# icesio2.net
KiCad netlist of a schematic drawn in EAGLE
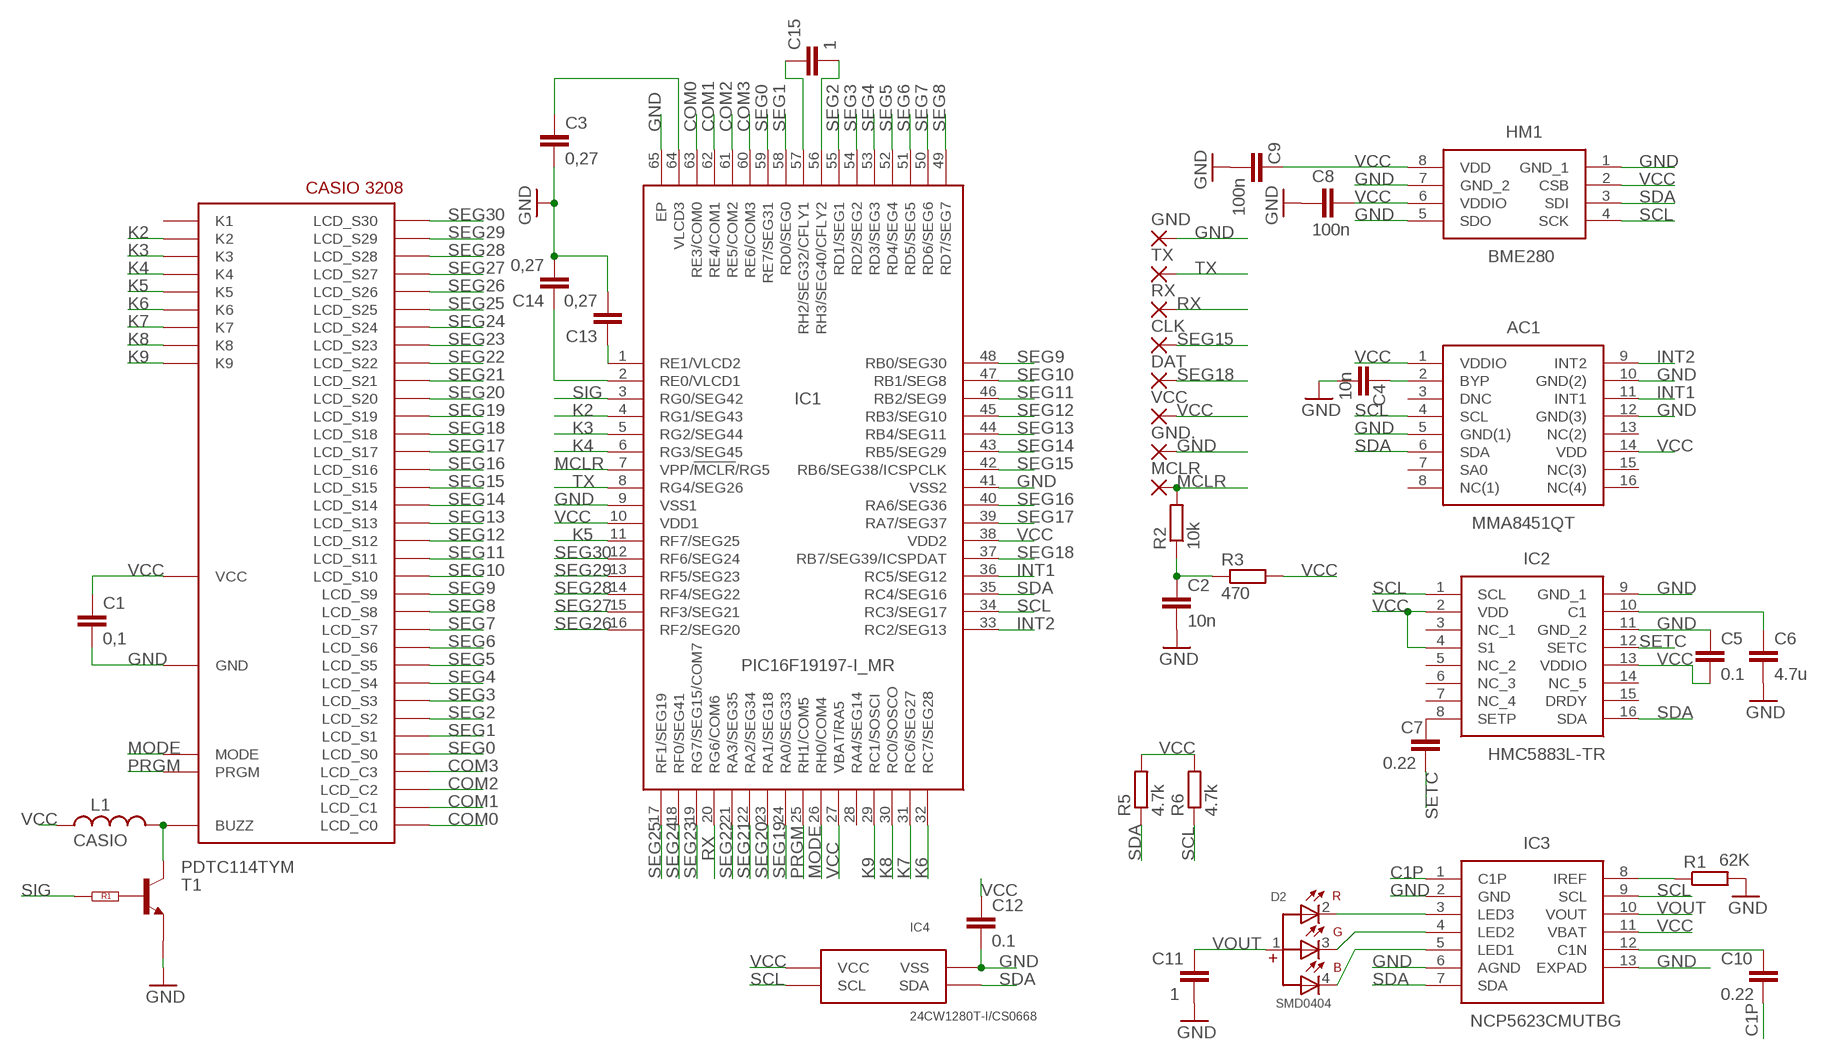
[diagram p0: schematic, sheet 1]

(export (version "E")
  (design (tool "Eeschema 10.0.6"))
  (components
    (comp (ref "AC1")
      (value "MMA8451QT")
      (footprint "eagle-import:PQFN50P300X300X100-16N")
      (fields
        (field (name "MANUFACTURER_PART_NUMBER") "mma8451qt")
        (field (name "RS_PART_NUMBER") "8212220P")
      )
      (libsource (lib "eagle-import") (part "MMA8451QT"))
    )
    (comp (ref "C1")
      (value "0,1")
      (footprint "eagle-import:RESC0402_L")
      (libsource (lib "eagle-import") (part "CAPACITOR_0402_L"))
    )
    (comp (ref "C2")
      (value "10n")
      (footprint "eagle-import:RESC0402_L")
      (libsource (lib "eagle-import") (part "CAPACITOR_0402_L"))
    )
    (comp (ref "C3")
      (value "0,27")
      (footprint "eagle-import:RESC0402_L")
      (libsource (lib "eagle-import") (part "CAPACITOR_0402_L"))
    )
    (comp (ref "C4")
      (value "10n")
      (footprint "eagle-import:RESC0402_L")
      (libsource (lib "eagle-import") (part "CAPACITOR_0402_L"))
    )
    (comp (ref "C5")
      (value "0.1")
      (footprint "eagle-import:RESC0402_L")
      (libsource (lib "eagle-import") (part "CAPACITOR_0402_L"))
    )
    (comp (ref "C6")
      (value "4.7u")
      (footprint "eagle-import:RESC0402_L")
      (libsource (lib "eagle-import") (part "CAPACITOR_0402_L"))
    )
    (comp (ref "C7")
      (value "0.22")
      (footprint "eagle-import:RESC0402_L")
      (libsource (lib "eagle-import") (part "CAPACITOR_0402_L"))
    )
    (comp (ref "C8")
      (value "100n")
      (footprint "eagle-import:RESC0402_L")
      (libsource (lib "eagle-import") (part "CAPACITOR_0402_L"))
    )
    (comp (ref "C9")
      (value "100n")
      (footprint "eagle-import:RESC0402_L")
      (libsource (lib "eagle-import") (part "CAPACITOR_0402_L"))
    )
    (comp (ref "C10")
      (value "0.22")
      (footprint "eagle-import:RESC0402_L")
      (libsource (lib "eagle-import") (part "CAPACITOR_0402_L"))
    )
    (comp (ref "C11")
      (value "1")
      (footprint "eagle-import:RESC0402_L")
      (libsource (lib "eagle-import") (part "CAPACITOR_0402_L"))
    )
    (comp (ref "C12")
      (value "0.1")
      (footprint "eagle-import:RESC0402_L")
      (libsource (lib "eagle-import") (part "CAPACITOR_0402_L"))
    )
    (comp (ref "C13")
      (value "0,27")
      (footprint "eagle-import:RESC0402_L")
      (libsource (lib "eagle-import") (part "CAPACITOR_0402_L"))
    )
    (comp (ref "C14")
      (value "0,27")
      (footprint "eagle-import:RESC0402_L")
      (libsource (lib "eagle-import") (part "CAPACITOR_0402_L"))
    )
    (comp (ref "C15")
      (value "1")
      (footprint "eagle-import:RESC0402_L")
      (libsource (lib "eagle-import") (part "CAPACITOR_0402_L"))
    )
    (comp (ref "CLK")
      (value "WIREPADSMD1,27-254")
      (footprint "eagle-import:SMD1,27-2,54")
      (libsource (lib "eagle-import") (part "WIREPADSMD1,27-254"))
    )
    (comp (ref "D2")
      (value "SMD0404")
      (footprint "eagle-import:WL-SFCC_0404")
      (libsource (lib "eagle-import") (part "WL-SFCC_0404_150044M155260"))
    )
    (comp (ref "DAT")
      (value "WIREPADSMD1,27-254")
      (footprint "eagle-import:SMD1,27-2,54")
      (libsource (lib "eagle-import") (part "WIREPADSMD1,27-254"))
    )
    (comp (ref "GND")
      (value "WIREPADSMD1,27-254")
      (footprint "eagle-import:SMD1,27-2,54")
      (libsource (lib "eagle-import") (part "WIREPADSMD1,27-254"))
    )
    (comp (ref "GND.")
      (value "WIREPADSMD1,27-254")
      (footprint "eagle-import:SMD1,27-2,54")
      (libsource (lib "eagle-import") (part "WIREPADSMD1,27-254"))
    )
    (comp (ref "HM1")
      (value "BME280")
      (footprint "eagle-import:BME280")
      (fields (field (name "MOUSER_PART_NUMBER") "262-BME280"))
      (libsource (lib "eagle-import") (part "BME280"))
    )
    (comp (ref "IC1")
      (value "PIC16F19197-I_MR")
      (footprint "eagle-import:QFN50P900X900X100-65N")
      (fields (field (name "ARROW_PART_NUMBER") "PIC16F19197-I/MR"))
      (libsource (lib "eagle-import") (part "PIC16F19197-I_MR"))
    )
    (comp (ref "IC2")
      (value "HMC5883L-TR")
      (footprint "eagle-import:16-PIN-LPCC")
      (libsource (lib "eagle-import") (part "HMC5883L-TR"))
    )
    (comp (ref "IC3")
      (value "NCP5623CMUTBG")
      (footprint "eagle-import:NCP5623BMUTBG")
      (fields
        (field (name "MOUSER_PART_NUMBER") "863-NCP5623CMUTBG")
        (field (name "RS_PART_NUMBER") "7922118P")
      )
      (libsource (lib "eagle-import") (part "NCP5623CMUTBG"))
    )
    (comp (ref "IC4")
      (value "24CW1280T-I/CS0668")
      (footprint "eagle-import:CSP")
      (libsource (lib "eagle-import") (part "24CW1280T-I/CS0668"))
    )
    (comp (ref "L1")
      (value "CASIO")
      (footprint "eagle-import:L4516C")
      (libsource (lib "eagle-import") (part "L-USL4516C"))
    )
    (comp (ref "MCLR")
      (value "WIREPADSMD1,27-254")
      (footprint "eagle-import:SMD1,27-2,54")
      (libsource (lib "eagle-import") (part "WIREPADSMD1,27-254"))
    )
    (comp (ref "R1")
      (value "62K")
      (footprint "eagle-import:R0402")
      (libsource (lib "eagle-import") (part "R-EU_R0402"))
    )
    (comp (ref "R2")
      (value "10k")
      (footprint "eagle-import:R0402")
      (libsource (lib "eagle-import") (part "R-EU_R0402"))
    )
    (comp (ref "R3")
      (value "470")
      (footprint "eagle-import:R0402")
      (libsource (lib "eagle-import") (part "R-EU_R0402"))
    )
    (comp (ref "R5")
      (value "4.7k")
      (footprint "eagle-import:R0402")
      (libsource (lib "eagle-import") (part "R-EU_R0402"))
    )
    (comp (ref "R6")
      (value "4.7k")
      (footprint "eagle-import:R0402")
      (libsource (lib "eagle-import") (part "R-EU_R0402"))
    )
    (comp (ref "RX")
      (value "WIREPADSMD1,27-254")
      (footprint "eagle-import:SMD1,27-2,54")
      (libsource (lib "eagle-import") (part "WIREPADSMD1,27-254"))
    )
    (comp (ref "T1")
      (value "PDTC114TYM")
      (footprint "eagle-import:SOT883(B)")
      (libsource (lib "eagle-import") (part "PDTC114TMY"))
    )
    (comp (ref "TX")
      (value "WIREPADSMD1,27-254")
      (footprint "eagle-import:SMD1,27-2,54")
      (libsource (lib "eagle-import") (part "WIREPADSMD1,27-254"))
    )
    (comp (ref "U$1")
      (value "CASIO3208")
      (footprint "eagle-import:CASIO3208")
      (libsource (lib "eagle-import") (part "CASIO3208"))
    )
    (comp (ref "VCC")
      (value "WIREPADSMD1,27-254")
      (footprint "eagle-import:SMD1,27-2,54")
      (libsource (lib "eagle-import") (part "WIREPADSMD1,27-254"))
    )
  )
  (nets
    (net (code "1") (name "/C1P") (class "Default")
      (node (ref "C10") (pin "2") (pinfunction "2_2") (pintype "passive"))
      (node (ref "IC3") (pin "1") (pinfunction "C1P_1") (pintype "bidirectional"))
    )
    (net (code "2") (name "/COM0") (class "Default")
      (node (ref "IC1") (pin "63") (pinfunction "RE3/COM0_63") (pintype "bidirectional"))
      (node (ref "U$1") (pin "LCD1") (pinfunction "LCD_C0_LCD1") (pintype "bidirectional"))
    )
    (net (code "3") (name "/COM1") (class "Default")
      (node (ref "IC1") (pin "62") (pinfunction "RE4/COM1_62") (pintype "bidirectional"))
      (node (ref "U$1") (pin "LCD2") (pinfunction "LCD_C1_LCD2") (pintype "bidirectional"))
    )
    (net (code "4") (name "/COM2") (class "Default")
      (node (ref "IC1") (pin "61") (pinfunction "RE5/COM2_61") (pintype "bidirectional"))
      (node (ref "U$1") (pin "LCD3") (pinfunction "LCD_C2_LCD3") (pintype "bidirectional"))
    )
    (net (code "5") (name "/COM3") (class "Default")
      (node (ref "IC1") (pin "60") (pinfunction "RE6/COM3_60") (pintype "bidirectional"))
      (node (ref "U$1") (pin "LCD4") (pinfunction "LCD_C3_LCD4") (pintype "bidirectional"))
    )
    (net (code "6") (name "/INT1") (class "Default")
      (node (ref "AC1") (pin "11") (pinfunction "INT1_11") (pintype "input"))
      (node (ref "IC1") (pin "36") (pinfunction "RC5/SEG12_36") (pintype "bidirectional"))
    )
    (net (code "7") (name "/INT2") (class "Default")
      (node (ref "AC1") (pin "9") (pinfunction "INT2_9") (pintype "input"))
      (node (ref "IC1") (pin "33") (pinfunction "RC2/SEG13_33") (pintype "bidirectional"))
    )
    (net (code "8") (name "/K2") (class "Default")
      (node (ref "IC1") (pin "4") (pinfunction "RG1/SEG43_4") (pintype "bidirectional"))
      (node (ref "U$1") (pin "K2") (pinfunction "K2_K2") (pintype "bidirectional"))
    )
    (net (code "9") (name "/K3") (class "Default")
      (node (ref "IC1") (pin "5") (pinfunction "RG2/SEG44_5") (pintype "bidirectional"))
      (node (ref "U$1") (pin "K3") (pinfunction "K3_K3") (pintype "bidirectional"))
    )
    (net (code "10") (name "/K4") (class "Default")
      (node (ref "IC1") (pin "6") (pinfunction "RG3/SEG45_6") (pintype "bidirectional"))
      (node (ref "U$1") (pin "K4") (pinfunction "K4_K4") (pintype "bidirectional"))
    )
    (net (code "11") (name "/K5") (class "Default")
      (node (ref "IC1") (pin "11") (pinfunction "RF7/SEG25_11") (pintype "bidirectional"))
      (node (ref "U$1") (pin "K5") (pinfunction "K5_K5") (pintype "bidirectional"))
    )
    (net (code "12") (name "/K6") (class "Default")
      (node (ref "IC1") (pin "32") (pinfunction "RC7/SEG28_32") (pintype "bidirectional"))
      (node (ref "U$1") (pin "K6") (pinfunction "K6_K6") (pintype "bidirectional"))
    )
    (net (code "13") (name "/K7") (class "Default")
      (node (ref "IC1") (pin "31") (pinfunction "RC6/SEG27_31") (pintype "bidirectional"))
      (node (ref "U$1") (pin "K7") (pinfunction "K7_K7") (pintype "bidirectional"))
    )
    (net (code "14") (name "/K8") (class "Default")
      (node (ref "IC1") (pin "30") (pinfunction "RC0/SOSCO_30") (pintype "bidirectional"))
      (node (ref "U$1") (pin "K8") (pinfunction "K8_K8") (pintype "bidirectional"))
    )
    (net (code "15") (name "/K9") (class "Default")
      (node (ref "IC1") (pin "29") (pinfunction "RC1/SOSCI_29") (pintype "bidirectional"))
      (node (ref "U$1") (pin "K9") (pinfunction "K9_K9") (pintype "bidirectional"))
    )
    (net (code "16") (name "/MCLR") (class "Default")
      (node (ref "IC1") (pin "7") (pinfunction "VPP/~{MCLR}/RG5_7") (pintype "bidirectional"))
      (node (ref "MCLR") (pin "1") (pinfunction "P_1") (pintype "passive"))
      (node (ref "R2") (pin "2") (pinfunction "2_2") (pintype "passive"))
    )
    (net (code "17") (name "/MODE") (class "Default")
      (node (ref "IC1") (pin "26") (pinfunction "RH0/COM4_26") (pintype "bidirectional"))
      (node (ref "U$1") (pin "MODE") (pinfunction "MODE_MODE") (pintype "bidirectional"))
    )
    (net (code "18") (name "/PRGM") (class "Default")
      (node (ref "IC1") (pin "25") (pinfunction "RH1/COM5_25") (pintype "bidirectional"))
      (node (ref "U$1") (pin "PRGM") (pinfunction "PRGM_PRGM") (pintype "bidirectional"))
    )
    (net (code "19") (name "/RX") (class "Default")
      (node (ref "IC1") (pin "20") (pinfunction "RG6/COM6_20") (pintype "bidirectional"))
      (node (ref "RX") (pin "1") (pinfunction "P_1") (pintype "passive"))
    )
    (net (code "20") (name "/SCL") (class "Default")
      (node (ref "AC1") (pin "4") (pinfunction "SCL_4") (pintype "passive"))
      (node (ref "HM1") (pin "4") (pinfunction "SCK_4") (pintype "bidirectional"))
      (node (ref "IC1") (pin "34") (pinfunction "RC3/SEG17_34") (pintype "bidirectional"))
      (node (ref "IC2") (pin "1") (pinfunction "SCL_1") (pintype "bidirectional"))
      (node (ref "IC3") (pin "9") (pinfunction "SCL_9") (pintype "bidirectional"))
      (node (ref "IC4") (pin "SCL") (pinfunction "SCL_SCL") (pintype "bidirectional"))
      (node (ref "R6") (pin "1") (pinfunction "1_1") (pintype "passive"))
    )
    (net (code "21") (name "/SDA") (class "Default")
      (node (ref "AC1") (pin "6") (pinfunction "SDA_6") (pintype "passive"))
      (node (ref "HM1") (pin "3") (pinfunction "SDI_3") (pintype "bidirectional"))
      (node (ref "IC1") (pin "35") (pinfunction "RC4/SEG16_35") (pintype "bidirectional"))
      (node (ref "IC2") (pin "16") (pinfunction "SDA_16") (pintype "bidirectional"))
      (node (ref "IC3") (pin "7") (pinfunction "SDA_7") (pintype "bidirectional"))
      (node (ref "IC4") (pin "SDA") (pinfunction "SDA_SDA") (pintype "bidirectional"))
      (node (ref "R5") (pin "1") (pinfunction "1_1") (pintype "passive"))
    )
    (net (code "22") (name "/SEG0") (class "Default")
      (node (ref "IC1") (pin "59") (pinfunction "RE7/SEG31_59") (pintype "bidirectional"))
      (node (ref "U$1") (pin "LCD5") (pinfunction "LCD_S0_LCD5") (pintype "bidirectional"))
    )
    (net (code "23") (name "/SEG1") (class "Default")
      (node (ref "IC1") (pin "58") (pinfunction "RD0/SEG0_58") (pintype "bidirectional"))
      (node (ref "U$1") (pin "LCD6") (pinfunction "LCD_S1_LCD6") (pintype "bidirectional"))
    )
    (net (code "24") (name "/SEG2") (class "Default")
      (node (ref "IC1") (pin "55") (pinfunction "RD1/SEG1_55") (pintype "bidirectional"))
      (node (ref "U$1") (pin "LCD7") (pinfunction "LCD_S2_LCD7") (pintype "bidirectional"))
    )
    (net (code "25") (name "/SEG3") (class "Default")
      (node (ref "IC1") (pin "54") (pinfunction "RD2/SEG2_54") (pintype "bidirectional"))
      (node (ref "U$1") (pin "LCD8") (pinfunction "LCD_S3_LCD8") (pintype "bidirectional"))
    )
    (net (code "26") (name "/SEG4") (class "Default")
      (node (ref "IC1") (pin "53") (pinfunction "RD3/SEG3_53") (pintype "bidirectional"))
      (node (ref "U$1") (pin "LCD9") (pinfunction "LCD_S4_LCD9") (pintype "bidirectional"))
    )
    (net (code "27") (name "/SEG5") (class "Default")
      (node (ref "IC1") (pin "52") (pinfunction "RD4/SEG4_52") (pintype "bidirectional"))
      (node (ref "U$1") (pin "LCD10") (pinfunction "LCD_S5_LCD10") (pintype "bidirectional"))
    )
    (net (code "28") (name "/SEG6") (class "Default")
      (node (ref "IC1") (pin "51") (pinfunction "RD5/SEG5_51") (pintype "bidirectional"))
      (node (ref "U$1") (pin "LCD11") (pinfunction "LCD_S6_LCD11") (pintype "bidirectional"))
    )
    (net (code "29") (name "/SEG7") (class "Default")
      (node (ref "IC1") (pin "50") (pinfunction "RD6/SEG6_50") (pintype "bidirectional"))
      (node (ref "U$1") (pin "LCD12") (pinfunction "LCD_S7_LCD12") (pintype "bidirectional"))
    )
    (net (code "30") (name "/SEG8") (class "Default")
      (node (ref "IC1") (pin "49") (pinfunction "RD7/SEG7_49") (pintype "bidirectional"))
      (node (ref "U$1") (pin "LCD13") (pinfunction "LCD_S8_LCD13") (pintype "bidirectional"))
    )
    (net (code "31") (name "/SEG9") (class "Default")
      (node (ref "IC1") (pin "48") (pinfunction "RB0/SEG30_48") (pintype "bidirectional"))
      (node (ref "U$1") (pin "LCD14") (pinfunction "LCD_S9_LCD14") (pintype "bidirectional"))
    )
    (net (code "32") (name "/SEG10") (class "Default")
      (node (ref "IC1") (pin "47") (pinfunction "RB1/SEG8_47") (pintype "bidirectional"))
      (node (ref "U$1") (pin "LCD15") (pinfunction "LCD_S10_LCD15") (pintype "bidirectional"))
    )
    (net (code "33") (name "/SEG11") (class "Default")
      (node (ref "IC1") (pin "46") (pinfunction "RB2/SEG9_46") (pintype "bidirectional"))
      (node (ref "U$1") (pin "LCD16") (pinfunction "LCD_S11_LCD16") (pintype "bidirectional"))
    )
    (net (code "34") (name "/SEG12") (class "Default")
      (node (ref "IC1") (pin "45") (pinfunction "RB3/SEG10_45") (pintype "bidirectional"))
      (node (ref "U$1") (pin "LCD17") (pinfunction "LCD_S12_LCD17") (pintype "bidirectional"))
    )
    (net (code "35") (name "/SEG13") (class "Default")
      (node (ref "IC1") (pin "44") (pinfunction "RB4/SEG11_44") (pintype "bidirectional"))
      (node (ref "U$1") (pin "LCD18") (pinfunction "LCD_S13_LCD18") (pintype "bidirectional"))
    )
    (net (code "36") (name "/SEG14") (class "Default")
      (node (ref "IC1") (pin "43") (pinfunction "RB5/SEG29_43") (pintype "bidirectional"))
      (node (ref "U$1") (pin "LCD19") (pinfunction "LCD_S14_LCD19") (pintype "bidirectional"))
    )
    (net (code "37") (name "/SEG15") (class "Default")
      (node (ref "CLK") (pin "1") (pinfunction "P_1") (pintype "passive"))
      (node (ref "IC1") (pin "42") (pinfunction "RB6/SEG38/ICSPCLK_42") (pintype "bidirectional"))
      (node (ref "U$1") (pin "LCD20") (pinfunction "LCD_S15_LCD20") (pintype "bidirectional"))
    )
    (net (code "38") (name "/SEG16") (class "Default")
      (node (ref "IC1") (pin "40") (pinfunction "RA6/SEG36_40") (pintype "bidirectional"))
      (node (ref "U$1") (pin "LCD21") (pinfunction "LCD_S16_LCD21") (pintype "bidirectional"))
    )
    (net (code "39") (name "/SEG17") (class "Default")
      (node (ref "IC1") (pin "39") (pinfunction "RA7/SEG37_39") (pintype "bidirectional"))
      (node (ref "U$1") (pin "LCD22") (pinfunction "LCD_S17_LCD22") (pintype "bidirectional"))
    )
    (net (code "40") (name "/SEG18") (class "Default")
      (node (ref "DAT") (pin "1") (pinfunction "P_1") (pintype "passive"))
      (node (ref "IC1") (pin "37") (pinfunction "RB7/SEG39/ICSPDAT_37") (pintype "bidirectional"))
      (node (ref "U$1") (pin "LCD23") (pinfunction "LCD_S18_LCD23") (pintype "bidirectional"))
    )
    (net (code "41") (name "/SEG19") (class "Default")
      (node (ref "IC1") (pin "24") (pinfunction "RA0/SEG33_24") (pintype "bidirectional"))
      (node (ref "U$1") (pin "LCD24") (pinfunction "LCD_S19_LCD24") (pintype "bidirectional"))
    )
    (net (code "42") (name "/SEG20") (class "Default")
      (node (ref "IC1") (pin "23") (pinfunction "RA1/SEG18_23") (pintype "bidirectional"))
      (node (ref "U$1") (pin "LCD25") (pinfunction "LCD_S20_LCD25") (pintype "bidirectional"))
    )
    (net (code "43") (name "/SEG21") (class "Default")
      (node (ref "IC1") (pin "22") (pinfunction "RA2/SEG34_22") (pintype "bidirectional"))
      (node (ref "U$1") (pin "LCD26") (pinfunction "LCD_S21_LCD26") (pintype "bidirectional"))
    )
    (net (code "44") (name "/SEG22") (class "Default")
      (node (ref "IC1") (pin "21") (pinfunction "RA3/SEG35_21") (pintype "bidirectional"))
      (node (ref "U$1") (pin "LCD27") (pinfunction "LCD_S22_LCD27") (pintype "bidirectional"))
    )
    (net (code "45") (name "/SEG23") (class "Default")
      (node (ref "IC1") (pin "19") (pinfunction "RG7/SEG15/COM7_19") (pintype "bidirectional"))
      (node (ref "U$1") (pin "LCD28") (pinfunction "LCD_S23_LCD28") (pintype "bidirectional"))
    )
    (net (code "46") (name "/SEG24") (class "Default")
      (node (ref "IC1") (pin "18") (pinfunction "RF0/SEG41_18") (pintype "bidirectional"))
      (node (ref "U$1") (pin "LCD29") (pinfunction "LCD_S24_LCD29") (pintype "bidirectional"))
    )
    (net (code "47") (name "/SEG25") (class "Default")
      (node (ref "IC1") (pin "17") (pinfunction "RF1/SEG19_17") (pintype "bidirectional"))
      (node (ref "U$1") (pin "LCD30") (pinfunction "LCD_S25_LCD30") (pintype "bidirectional"))
    )
    (net (code "48") (name "/SEG26") (class "Default")
      (node (ref "IC1") (pin "16") (pinfunction "RF2/SEG20_16") (pintype "bidirectional"))
      (node (ref "U$1") (pin "LCD31") (pinfunction "LCD_S26_LCD31") (pintype "bidirectional"))
    )
    (net (code "49") (name "/SEG27") (class "Default")
      (node (ref "IC1") (pin "15") (pinfunction "RF3/SEG21_15") (pintype "bidirectional"))
      (node (ref "U$1") (pin "LCD32") (pinfunction "LCD_S27_LCD32") (pintype "bidirectional"))
    )
    (net (code "50") (name "/SEG28") (class "Default")
      (node (ref "IC1") (pin "14") (pinfunction "RF4/SEG22_14") (pintype "bidirectional"))
      (node (ref "U$1") (pin "LCD33") (pinfunction "LCD_S28_LCD33") (pintype "bidirectional"))
    )
    (net (code "51") (name "/SEG29") (class "Default")
      (node (ref "IC1") (pin "13") (pinfunction "RF5/SEG23_13") (pintype "bidirectional"))
      (node (ref "U$1") (pin "LCD34") (pinfunction "LCD_S29_LCD34") (pintype "bidirectional"))
    )
    (net (code "52") (name "/SEG30") (class "Default")
      (node (ref "IC1") (pin "12") (pinfunction "RF6/SEG24_12") (pintype "bidirectional"))
      (node (ref "U$1") (pin "LCD35") (pinfunction "LCD_S30_LCD35") (pintype "bidirectional"))
    )
    (net (code "53") (name "/SETC") (class "Default")
      (node (ref "C7") (pin "2") (pinfunction "2_2") (pintype "passive"))
      (node (ref "IC2") (pin "12") (pinfunction "SETC_12") (pintype "bidirectional"))
    )
    (net (code "54") (name "/SIG") (class "Default")
      (node (ref "IC1") (pin "3") (pinfunction "RG0/SEG42_3") (pintype "bidirectional"))
      (node (ref "T1") (pin "1") (pinfunction "INPUT_1") (pintype "passive"))
    )
    (net (code "55") (name "/TX") (class "Default")
      (node (ref "IC1") (pin "8") (pinfunction "RG4/SEG26_8") (pintype "bidirectional"))
      (node (ref "TX") (pin "1") (pinfunction "P_1") (pintype "passive"))
    )
    (net (code "56") (name "/VCC") (class "Default")
      (node (ref "AC1") (pin "1") (pinfunction "VDDIO_1") (pintype "power_in"))
      (node (ref "AC1") (pin "14") (pinfunction "VDD_14") (pintype "power_in"))
      (node (ref "C1") (pin "1") (pinfunction "1_1") (pintype "passive"))
      (node (ref "C12") (pin "1") (pinfunction "1_1") (pintype "passive"))
      (node (ref "C5") (pin "2") (pinfunction "2_2") (pintype "passive"))
      (node (ref "C8") (pin "1") (pinfunction "1_1") (pintype "passive"))
      (node (ref "C9") (pin "1") (pinfunction "1_1") (pintype "passive"))
      (node (ref "HM1") (pin "2") (pinfunction "CSB_2") (pintype "input"))
      (node (ref "HM1") (pin "6") (pinfunction "VDDIO_6") (pintype "power_in"))
      (node (ref "HM1") (pin "8") (pinfunction "VDD_8") (pintype "power_in"))
      (node (ref "IC1") (pin "10") (pinfunction "VDD1_10") (pintype "bidirectional"))
      (node (ref "IC1") (pin "27") (pinfunction "VBAT/RA5_27") (pintype "bidirectional"))
      (node (ref "IC1") (pin "38") (pinfunction "VDD2_38") (pintype "bidirectional"))
      (node (ref "IC2") (pin "13") (pinfunction "VDDIO_13") (pintype "bidirectional"))
      (node (ref "IC2") (pin "2") (pinfunction "VDD_2") (pintype "bidirectional"))
      (node (ref "IC2") (pin "4") (pinfunction "S1_4") (pintype "bidirectional"))
      (node (ref "IC3") (pin "11") (pinfunction "VBAT_11") (pintype "bidirectional"))
      (node (ref "IC4") (pin "VCC") (pinfunction "VCC_VCC") (pintype "bidirectional"))
      (node (ref "L1") (pin "1") (pinfunction "1_1") (pintype "passive"))
      (node (ref "R3") (pin "2") (pinfunction "2_2") (pintype "passive"))
      (node (ref "R5") (pin "2") (pinfunction "2_2") (pintype "passive"))
      (node (ref "R6") (pin "2") (pinfunction "2_2") (pintype "passive"))
      (node (ref "U$1") (pin "VCC") (pinfunction "VCC_VCC") (pintype "bidirectional"))
      (node (ref "VCC") (pin "1") (pinfunction "P_1") (pintype "passive"))
    )
    (net (code "57") (name "/VOUT") (class "Default")
      (node (ref "C11") (pin "1") (pinfunction "1_1") (pintype "passive"))
      (node (ref "D2") (pin "1") (pinfunction "1_1") (pintype "passive"))
      (node (ref "IC3") (pin "10") (pinfunction "VOUT_10") (pintype "bidirectional"))
    )
    (net (code "58") (name "GND") (class "Default")
      (node (ref "AC1") (pin "10") (pinfunction "GND(2)_10") (pintype "power_in"))
      (node (ref "AC1") (pin "12") (pinfunction "GND(3)_12") (pintype "power_in"))
      (node (ref "AC1") (pin "5") (pinfunction "GND(1)_5") (pintype "power_in"))
      (node (ref "C1") (pin "2") (pinfunction "2_2") (pintype "passive"))
      (node (ref "C11") (pin "2") (pinfunction "2_2") (pintype "passive"))
      (node (ref "C12") (pin "2") (pinfunction "2_2") (pintype "passive"))
      (node (ref "C13") (pin "2") (pinfunction "2_2") (pintype "passive"))
      (node (ref "C14") (pin "2") (pinfunction "2_2") (pintype "passive"))
      (node (ref "C2") (pin "2") (pinfunction "2_2") (pintype "passive"))
      (node (ref "C3") (pin "2") (pinfunction "2_2") (pintype "passive"))
      (node (ref "C4") (pin "2") (pinfunction "2_2") (pintype "passive"))
      (node (ref "C5") (pin "1") (pinfunction "1_1") (pintype "passive"))
      (node (ref "C6") (pin "2") (pinfunction "2_2") (pintype "passive"))
      (node (ref "C8") (pin "2") (pinfunction "2_2") (pintype "passive"))
      (node (ref "C9") (pin "2") (pinfunction "2_2") (pintype "passive"))
      (node (ref "GND") (pin "1") (pinfunction "P_1") (pintype "passive"))
      (node (ref "GND.") (pin "1") (pinfunction "P_1") (pintype "passive"))
      (node (ref "HM1") (pin "1") (pinfunction "GND_1_1") (pintype "power_in"))
      (node (ref "HM1") (pin "5") (pinfunction "SDO_5") (pintype "bidirectional"))
      (node (ref "HM1") (pin "7") (pinfunction "GND_2_7") (pintype "power_in"))
      (node (ref "IC1") (pin "41") (pinfunction "VSS2_41") (pintype "bidirectional"))
      (node (ref "IC1") (pin "65") (pinfunction "EP_65") (pintype "bidirectional"))
      (node (ref "IC1") (pin "9") (pinfunction "VSS1_9") (pintype "bidirectional"))
      (node (ref "IC2") (pin "11") (pinfunction "GND_2_11") (pintype "bidirectional"))
      (node (ref "IC2") (pin "9") (pinfunction "GND_1_9") (pintype "bidirectional"))
      (node (ref "IC3") (pin "13") (pinfunction "EXPAD_13") (pintype "bidirectional"))
      (node (ref "IC3") (pin "2") (pinfunction "GND_2") (pintype "bidirectional"))
      (node (ref "IC3") (pin "6") (pinfunction "AGND_6") (pintype "bidirectional"))
      (node (ref "IC4") (pin "VSS") (pinfunction "VSS_VSS") (pintype "bidirectional"))
      (node (ref "R1") (pin "2") (pinfunction "2_2") (pintype "passive"))
      (node (ref "T1") (pin "2") (pinfunction "E_2") (pintype "passive"))
      (node (ref "U$1") (pin "GND") (pinfunction "GND_GND") (pintype "bidirectional"))
    )
    (net (code "59") (name "Net-(AC1-BYP)") (class "Default")
      (node (ref "AC1") (pin "2") (pinfunction "BYP_2") (pintype "passive"))
      (node (ref "C4") (pin "1") (pinfunction "1_1") (pintype "passive"))
    )
    (net (code "60") (name "Net-(C2-Pad1)") (class "Default")
      (node (ref "C2") (pin "1") (pinfunction "1_1") (pintype "passive"))
      (node (ref "R2") (pin "1") (pinfunction "1_1") (pintype "passive"))
      (node (ref "R3") (pin "1") (pinfunction "1_1") (pintype "passive"))
    )
    (net (code "61") (name "Net-(D2-B)") (class "Default")
      (node (ref "D2") (pin "4") (pinfunction "B_4") (pintype "passive"))
      (node (ref "IC3") (pin "5") (pinfunction "LED1_5") (pintype "bidirectional"))
    )
    (net (code "62") (name "Net-(D2-G)") (class "Default")
      (node (ref "D2") (pin "3") (pinfunction "G_3") (pintype "passive"))
      (node (ref "IC3") (pin "4") (pinfunction "LED2_4") (pintype "bidirectional"))
    )
    (net (code "63") (name "Net-(D2-R)") (class "Default")
      (node (ref "D2") (pin "2") (pinfunction "R_2") (pintype "passive"))
      (node (ref "IC3") (pin "3") (pinfunction "LED3_3") (pintype "bidirectional"))
    )
    (net (code "64") (name "Net-(IC1-RE0{slash}VLCD1)") (class "Default")
      (node (ref "C14") (pin "1") (pinfunction "1_1") (pintype "passive"))
      (node (ref "IC1") (pin "2") (pinfunction "RE0/VLCD1_2") (pintype "bidirectional"))
    )
    (net (code "65") (name "Net-(IC1-RE1{slash}VLCD2)") (class "Default")
      (node (ref "C13") (pin "1") (pinfunction "1_1") (pintype "passive"))
      (node (ref "IC1") (pin "1") (pinfunction "RE1/VLCD2_1") (pintype "bidirectional"))
    )
    (net (code "66") (name "Net-(IC1-RH2{slash}SEG32{slash}CFLY1)") (class "Default")
      (node (ref "C15") (pin "1") (pinfunction "1_1") (pintype "passive"))
      (node (ref "IC1") (pin "57") (pinfunction "RH2/SEG32/CFLY1_57") (pintype "bidirectional"))
    )
    (net (code "67") (name "Net-(IC1-RH3{slash}SEG40{slash}CFLY2)") (class "Default")
      (node (ref "C15") (pin "2") (pinfunction "2_2") (pintype "passive"))
      (node (ref "IC1") (pin "56") (pinfunction "RH3/SEG40/CFLY2_56") (pintype "bidirectional"))
    )
    (net (code "68") (name "Net-(IC1-VLCD3)") (class "Default")
      (node (ref "C3") (pin "1") (pinfunction "1_1") (pintype "passive"))
      (node (ref "IC1") (pin "64") (pinfunction "VLCD3_64") (pintype "bidirectional"))
    )
    (net (code "69") (name "Net-(IC2-C1)") (class "Default")
      (node (ref "C6") (pin "1") (pinfunction "1_1") (pintype "passive"))
      (node (ref "IC2") (pin "10") (pinfunction "C1_10") (pintype "bidirectional"))
    )
    (net (code "70") (name "Net-(IC2-SETP)") (class "Default")
      (node (ref "C7") (pin "1") (pinfunction "1_1") (pintype "passive"))
      (node (ref "IC2") (pin "8") (pinfunction "SETP_8") (pintype "bidirectional"))
    )
    (net (code "71") (name "Net-(IC3-C1N)") (class "Default")
      (node (ref "C10") (pin "1") (pinfunction "1_1") (pintype "passive"))
      (node (ref "IC3") (pin "12") (pinfunction "C1N_12") (pintype "bidirectional"))
    )
    (net (code "72") (name "Net-(IC3-IREF)") (class "Default")
      (node (ref "IC3") (pin "8") (pinfunction "IREF_8") (pintype "bidirectional"))
      (node (ref "R1") (pin "1") (pinfunction "1_1") (pintype "passive"))
    )
    (net (code "73") (name "Net-(T1-C)") (class "Default")
      (node (ref "L1") (pin "2") (pinfunction "2_2") (pintype "passive"))
      (node (ref "T1") (pin "3") (pinfunction "C_3") (pintype "passive"))
      (node (ref "U$1") (pin "BUZZ") (pinfunction "BUZZ_BUZZ") (pintype "bidirectional"))
    )
    (net (code "74") (name "unconnected-(AC1-DNC-Pad3)") (class "Default")
      (node (ref "AC1") (pin "3") (pinfunction "DNC_3") (pintype "passive"))
    )
    (net (code "75") (name "unconnected-(AC1-NC(1)-Pad8)") (class "Default")
      (node (ref "AC1") (pin "8") (pinfunction "NC(1)_8") (pintype "passive"))
    )
    (net (code "76") (name "unconnected-(AC1-NC(2)-Pad13)") (class "Default")
      (node (ref "AC1") (pin "13") (pinfunction "NC(2)_13") (pintype "passive"))
    )
    (net (code "77") (name "unconnected-(AC1-NC(3)-Pad15)") (class "Default")
      (node (ref "AC1") (pin "15") (pinfunction "NC(3)_15") (pintype "passive"))
    )
    (net (code "78") (name "unconnected-(AC1-NC(4)-Pad16)") (class "Default")
      (node (ref "AC1") (pin "16") (pinfunction "NC(4)_16") (pintype "passive"))
    )
    (net (code "79") (name "unconnected-(AC1-SA0-Pad7)") (class "Default")
      (node (ref "AC1") (pin "7") (pinfunction "SA0_7") (pintype "passive"))
    )
    (net (code "80") (name "unconnected-(IC1-RA4{slash}SEG14-Pad28)") (class "Default")
      (node (ref "IC1") (pin "28") (pinfunction "RA4/SEG14_28") (pintype "bidirectional"))
    )
    (net (code "81") (name "unconnected-(IC2-DRDY-Pad15)") (class "Default")
      (node (ref "IC2") (pin "15") (pinfunction "DRDY_15") (pintype "bidirectional"))
    )
    (net (code "82") (name "unconnected-(IC2-NC_1-Pad3)") (class "Default")
      (node (ref "IC2") (pin "3") (pinfunction "NC_1_3") (pintype "bidirectional"))
    )
    (net (code "83") (name "unconnected-(IC2-NC_2-Pad5)") (class "Default")
      (node (ref "IC2") (pin "5") (pinfunction "NC_2_5") (pintype "bidirectional"))
    )
    (net (code "84") (name "unconnected-(IC2-NC_3-Pad6)") (class "Default")
      (node (ref "IC2") (pin "6") (pinfunction "NC_3_6") (pintype "bidirectional"))
    )
    (net (code "85") (name "unconnected-(IC2-NC_4-Pad7)") (class "Default")
      (node (ref "IC2") (pin "7") (pinfunction "NC_4_7") (pintype "bidirectional"))
    )
    (net (code "86") (name "unconnected-(IC2-NC_5-Pad14)") (class "Default")
      (node (ref "IC2") (pin "14") (pinfunction "NC_5_14") (pintype "bidirectional"))
    )
    (net (code "87") (name "unconnected-(U$1-PadK1)") (class "Default")
      (node (ref "U$1") (pin "K1") (pinfunction "K1_K1") (pintype "bidirectional"))
    )
  )
)
